# IP5306.net
KiCad netlist of a schematic drawn in EasyEDA Pro
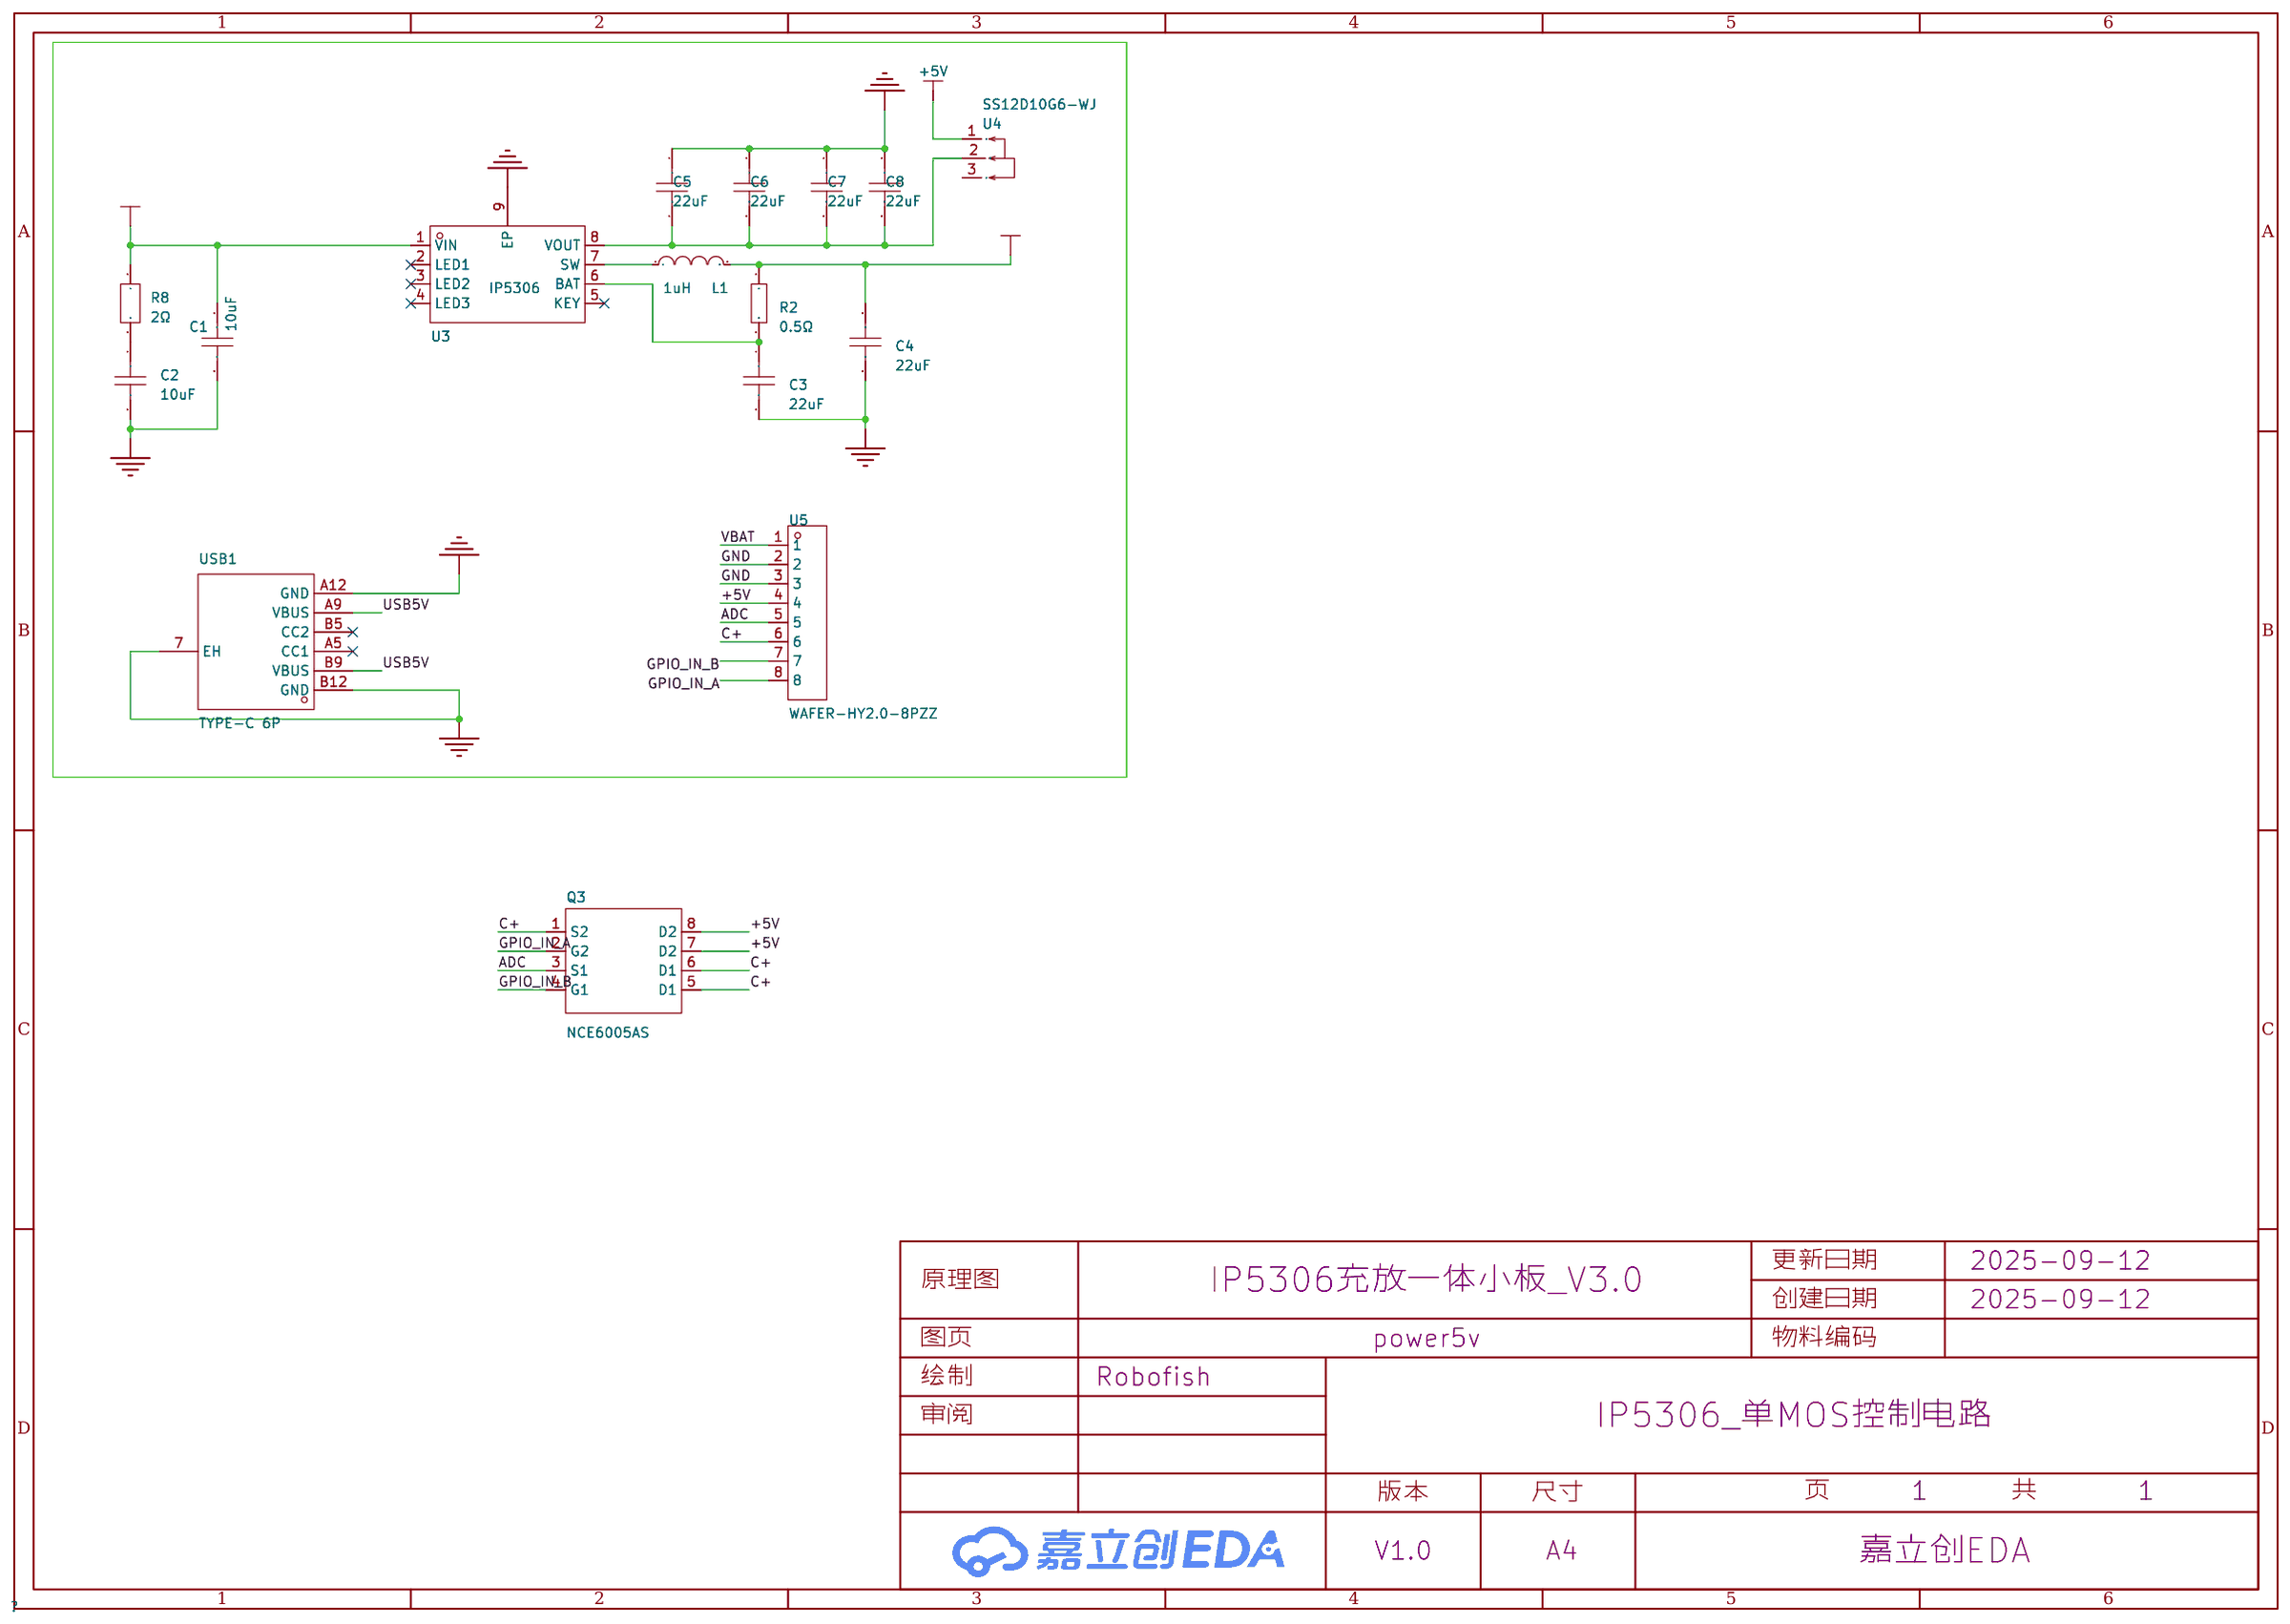
[diagram p0: schematic sheet]

(export (version "E")
  (design (tool "Eeschema 10.0.6"))
  (components
    (comp (ref "C1")
      (value "10uF")
      (footprint "easyedapro:C0805")
      (description "容值:10uF;精度:±10%;额定电压:25V;材质(温度系数):X5R;")
      (fields
        (field (name "Manufacturer Part") "CL21A106KAYNNNE")
        (field (name "Manufacturer") "SAMSUNG(三星)")
      )
      (libsource (lib "easyedapro") (part "CL21A106KAYNNNE"))
    )
    (comp (ref "C2")
      (value "10uF")
      (footprint "easyedapro:C0805")
      (description "容值:10uF;精度:±10%;额定电压:25V;材质(温度系数):X5R;")
      (fields
        (field (name "Manufacturer Part") "CL21A106KAYNNNE")
        (field (name "Manufacturer") "SAMSUNG(三星)")
      )
      (libsource (lib "easyedapro") (part "CL21A106KAYNNNE"))
    )
    (comp (ref "C3")
      (value "22uF")
      (footprint "easyedapro:C0805")
      (description "容值:22uF;精度:±20%;额定电压:25V;材质(温度系数):X5R;")
      (fields
        (field (name "Manufacturer Part") "CL21A226MAQNNNE")
        (field (name "Manufacturer") "SAMSUNG(三星)")
      )
      (libsource (lib "easyedapro") (part "CL21A226MAQNNNE"))
    )
    (comp (ref "C4")
      (value "22uF")
      (footprint "easyedapro:C0805")
      (description "容值:22uF;精度:±20%;额定电压:25V;材质(温度系数):X5R;")
      (fields
        (field (name "Manufacturer Part") "CL21A226MAQNNNE")
        (field (name "Manufacturer") "SAMSUNG(三星)")
      )
      (libsource (lib "easyedapro") (part "CL21A226MAQNNNE"))
    )
    (comp (ref "C5")
      (value "22uF")
      (footprint "easyedapro:C0805")
      (description "容值:22uF;精度:±20%;额定电压:25V;材质(温度系数):X5R;")
      (fields
        (field (name "Manufacturer Part") "CL21A226MAQNNNE")
        (field (name "Manufacturer") "SAMSUNG(三星)")
      )
      (libsource (lib "easyedapro") (part "CL21A226MAQNNNE"))
    )
    (comp (ref "C6")
      (value "22uF")
      (footprint "easyedapro:C0805")
      (description "容值:22uF;精度:±20%;额定电压:25V;材质(温度系数):X5R;")
      (fields
        (field (name "Manufacturer Part") "CL21A226MAQNNNE")
        (field (name "Manufacturer") "SAMSUNG(三星)")
      )
      (libsource (lib "easyedapro") (part "CL21A226MAQNNNE"))
    )
    (comp (ref "C7")
      (value "22uF")
      (footprint "easyedapro:C0805")
      (description "容值:22uF;精度:±20%;额定电压:25V;材质(温度系数):X5R;")
      (fields
        (field (name "Manufacturer Part") "CL21A226MAQNNNE")
        (field (name "Manufacturer") "SAMSUNG(三星)")
      )
      (libsource (lib "easyedapro") (part "CL21A226MAQNNNE"))
    )
    (comp (ref "C8")
      (value "22uF")
      (footprint "easyedapro:C0805")
      (description "容值:22uF;精度:±20%;额定电压:25V;材质(温度系数):X5R;")
      (fields
        (field (name "Manufacturer Part") "CL21A226MAQNNNE")
        (field (name "Manufacturer") "SAMSUNG(三星)")
      )
      (libsource (lib "easyedapro") (part "CL21A226MAQNNNE"))
    )
    (comp (ref "L1")
      (value "1uH")
      (footprint "easyedapro:IND-SMD_L4.4-W4.2")
      (description "电感值:1uH;精度:±20%;额定电流:6A;饱和电流(Isat):7A;类型:一体成型电感;")
      (fields (field (name "Manufacturer Part") "FXL0420-1R0-M") (field (name "Manufacturer") "cjiang(长江微电)"))
      (libsource (lib "easyedapro") (part "FXL0420-1R0-M"))
    )
    (comp (ref "Q3")
      (value "NCE6005AS")
      (footprint "easyedapro:SOP-8_L4.9-W3.9-P1.27-LS6.0-BL")
      (fields (field (name "Manufacturer") "NCE(无锡新洁能)"))
      (libsource (lib "easyedapro") (part "NCE6005AS"))
    )
    (comp (ref "R2")
      (value "0.5Ω")
      (footprint "easyedapro:R0805")
      (description "电阻类型:厚膜电阻;阻值:500mΩ;精度:±1%;功率:125mW;最大工作电压:150V;温度系数:±800ppm/°C;")
      (fields
        (field (name "Manufacturer Part") "0805W8F500LT5E")
        (field (name "Manufacturer") "UNI-ROYAL(厚声)")
      )
      (libsource (lib "easyedapro") (part "0805W8F500LT5E"))
    )
    (comp (ref "R8")
      (value "2Ω")
      (footprint "easyedapro:R1206")
      (description "电阻类型:采样电阻;阻值:100mΩ;精度:±1%;功率:1W;温度系数:±50ppm/°C;")
      (fields (field (name "Manufacturer Part") "RE1206F1R100") (field (name "Manufacturer") "捷而瑞"))
      (libsource (lib "easyedapro") (part "RE1206F1R100"))
    )
    (comp (ref "U3")
      (value "IP5306")
      (footprint "easyedapro:ESOP-8_L4.9-W3.9-P1.27-LS6.0-BL-EP")
      (description "2.1A充电2.4A放电高集成度移动电源SOC")
      (fields (field (name "Manufacturer") "INJOINIC(英集芯)"))
      (libsource (lib "easyedapro") (part "IP5306"))
    )
    (comp (ref "U4")
      (value "SS12D10G6-WJ")
      (footprint "easyedapro:SW-TH_3P-P4.80_HX-SS12D10G6-WJ")
      (description "电路结构:单刀双掷;安装方式:弯插;开关颜色:黑色;额定电流:2A;额定电压:125V;工作寿命:3千次;")
      (fields (field (name "Manufacturer") "SHOU HAN(首韩)"))
      (libsource (lib "easyedapro") (part "SS12D10G6-WJ"))
    )
    (comp (ref "U5")
      (value "WAFER-HY2.0-8PZZ")
      (footprint "easyedapro:CONN-TH_8P-P2.00_WAFER-HY2.0-8PZZ")
      (fields (field (name "Manufacturer") "XUNPU(讯普)"))
      (libsource (lib "easyedapro") (part "WAFER-HY2.0-8PZZ"))
    )
    (comp (ref "USB1")
      (value "TYPE-C 6P")
      (footprint "easyedapro:TYPE-C-SMD_TYPE-C-6P")
      (description "连接器类型:Type-C;标准:USB 3.1;公母:母;安装方式:卧贴;触点数量:6P;端口数量:1;额定电流 - 电源:5A;工作温度范围:-40°C~+85°C;")
      (fields (field (name "Manufacturer") "SHOU HAN(首韩)"))
      (libsource (lib "easyedapro") (part "TYPE-C 6P"))
    )
  )
  (nets
    (net (code "1") (name "+5V") (class "Default")
      (node (ref "Q3") (pin "7") (pinfunction "D2_7") (pintype "unspecified"))
      (node (ref "Q3") (pin "8") (pinfunction "D2_8") (pintype "unspecified"))
      (node (ref "U4") (pin "1") (pinfunction "1_1") (pintype "unspecified"))
      (node (ref "U5") (pin "4") (pinfunction "4_4") (pintype "unspecified"))
    )
    (net (code "2") (name "/ADC") (class "Default")
      (node (ref "Q3") (pin "3") (pinfunction "S1_3") (pintype "unspecified"))
      (node (ref "U5") (pin "5") (pinfunction "5_5") (pintype "unspecified"))
    )
    (net (code "3") (name "/C+") (class "Default")
      (node (ref "Q3") (pin "1") (pinfunction "S2_1") (pintype "unspecified"))
      (node (ref "Q3") (pin "5") (pinfunction "D1_5") (pintype "unspecified"))
      (node (ref "Q3") (pin "6") (pinfunction "D1_6") (pintype "unspecified"))
      (node (ref "U5") (pin "6") (pinfunction "6_6") (pintype "unspecified"))
    )
    (net (code "4") (name "/GPIO_IN_A") (class "Default")
      (node (ref "Q3") (pin "2") (pinfunction "G2_2") (pintype "unspecified"))
      (node (ref "U5") (pin "8") (pinfunction "8_8") (pintype "unspecified"))
    )
    (net (code "5") (name "/GPIO_IN_B") (class "Default")
      (node (ref "Q3") (pin "4") (pinfunction "G1_4") (pintype "unspecified"))
      (node (ref "U5") (pin "7") (pinfunction "7_7") (pintype "unspecified"))
    )
    (net (code "6") (name "GND") (class "Default")
      (node (ref "C1") (pin "2") (pinfunction "2_2") (pintype "unspecified"))
      (node (ref "C2") (pin "2") (pinfunction "2_2") (pintype "unspecified"))
      (node (ref "C3") (pin "2") (pinfunction "2_2") (pintype "unspecified"))
      (node (ref "C4") (pin "2") (pinfunction "2_2") (pintype "unspecified"))
      (node (ref "C5") (pin "1") (pinfunction "1_1") (pintype "unspecified"))
      (node (ref "C6") (pin "1") (pinfunction "1_1") (pintype "unspecified"))
      (node (ref "C7") (pin "1") (pinfunction "1_1") (pintype "unspecified"))
      (node (ref "C8") (pin "1") (pinfunction "1_1") (pintype "unspecified"))
      (node (ref "U3") (pin "9") (pinfunction "EP_9") (pintype "unspecified"))
      (node (ref "U5") (pin "2") (pinfunction "2_2") (pintype "unspecified"))
      (node (ref "U5") (pin "3") (pinfunction "3_3") (pintype "unspecified"))
      (node (ref "USB1") (pin "7") (pinfunction "EH_7") (pintype "unspecified"))
      (node (ref "USB1") (pin "A12") (pinfunction "GND_A12") (pintype "unspecified"))
      (node (ref "USB1") (pin "B12") (pinfunction "GND_B12") (pintype "unspecified"))
    )
    (net (code "7") (name "Net-(C2-Pad1)") (class "Default")
      (node (ref "C2") (pin "1") (pinfunction "1_1") (pintype "unspecified"))
      (node (ref "R8") (pin "2") (pinfunction "2_2") (pintype "unspecified"))
    )
    (net (code "8") (name "Net-(U3-BAT)") (class "Default")
      (node (ref "C3") (pin "1") (pinfunction "1_1") (pintype "unspecified"))
      (node (ref "R2") (pin "2") (pinfunction "2_2") (pintype "input"))
      (node (ref "U3") (pin "6") (pinfunction "BAT_6") (pintype "unspecified"))
    )
    (net (code "9") (name "Net-(U3-SW)") (class "Default")
      (node (ref "L1") (pin "1") (pinfunction "1_1") (pintype "unspecified"))
      (node (ref "U3") (pin "7") (pinfunction "SW_7") (pintype "unspecified"))
    )
    (net (code "10") (name "Net-(U3-VOUT)") (class "Default")
      (node (ref "C5") (pin "2") (pinfunction "2_2") (pintype "unspecified"))
      (node (ref "C6") (pin "2") (pinfunction "2_2") (pintype "unspecified"))
      (node (ref "C7") (pin "2") (pinfunction "2_2") (pintype "unspecified"))
      (node (ref "C8") (pin "2") (pinfunction "2_2") (pintype "unspecified"))
      (node (ref "U3") (pin "8") (pinfunction "VOUT_8") (pintype "unspecified"))
      (node (ref "U4") (pin "2") (pinfunction "2_2") (pintype "unspecified"))
    )
    (net (code "11") (name "USB5V") (class "Default")
      (node (ref "C1") (pin "1") (pinfunction "1_1") (pintype "unspecified"))
      (node (ref "R8") (pin "1") (pinfunction "1_1") (pintype "unspecified"))
      (node (ref "U3") (pin "1") (pinfunction "VIN_1") (pintype "unspecified"))
      (node (ref "USB1") (pin "A9") (pinfunction "VBUS_A9") (pintype "unspecified"))
      (node (ref "USB1") (pin "B9") (pinfunction "VBUS_B9") (pintype "unspecified"))
    )
    (net (code "12") (name "VBAT") (class "Default")
      (node (ref "C4") (pin "1") (pinfunction "1_1") (pintype "unspecified"))
      (node (ref "L1") (pin "2") (pinfunction "2_2") (pintype "unspecified"))
      (node (ref "R2") (pin "1") (pinfunction "1_1") (pintype "input"))
      (node (ref "U5") (pin "1") (pinfunction "1_1") (pintype "unspecified"))
    )
    (net (code "13") (name "unconnected-(U3-KEY-Pad5)") (class "Default")
      (node (ref "U3") (pin "5") (pinfunction "KEY_5") (pintype "unspecified+no_connect"))
    )
    (net (code "14") (name "unconnected-(U3-LED1-Pad2)") (class "Default")
      (node (ref "U3") (pin "2") (pinfunction "LED1_2") (pintype "unspecified+no_connect"))
    )
    (net (code "15") (name "unconnected-(U3-LED2-Pad3)") (class "Default")
      (node (ref "U3") (pin "3") (pinfunction "LED2_3") (pintype "unspecified+no_connect"))
    )
    (net (code "16") (name "unconnected-(U3-LED3-Pad4)") (class "Default")
      (node (ref "U3") (pin "4") (pinfunction "LED3_4") (pintype "unspecified+no_connect"))
    )
    (net (code "17") (name "unconnected-(U4-Pad3)") (class "Default")
      (node (ref "U4") (pin "3") (pinfunction "3_3") (pintype "unspecified"))
    )
    (net (code "18") (name "unconnected-(USB1-CC1-PadA5)") (class "Default")
      (node (ref "USB1") (pin "A5") (pinfunction "CC1_A5") (pintype "unspecified+no_connect"))
    )
    (net (code "19") (name "unconnected-(USB1-CC2-PadB5)") (class "Default")
      (node (ref "USB1") (pin "B5") (pinfunction "CC2_B5") (pintype "unspecified+no_connect"))
    )
  )
)
